# 8x8matrix_alt.net
KiCad netlist of a schematic drawn in EAGLE
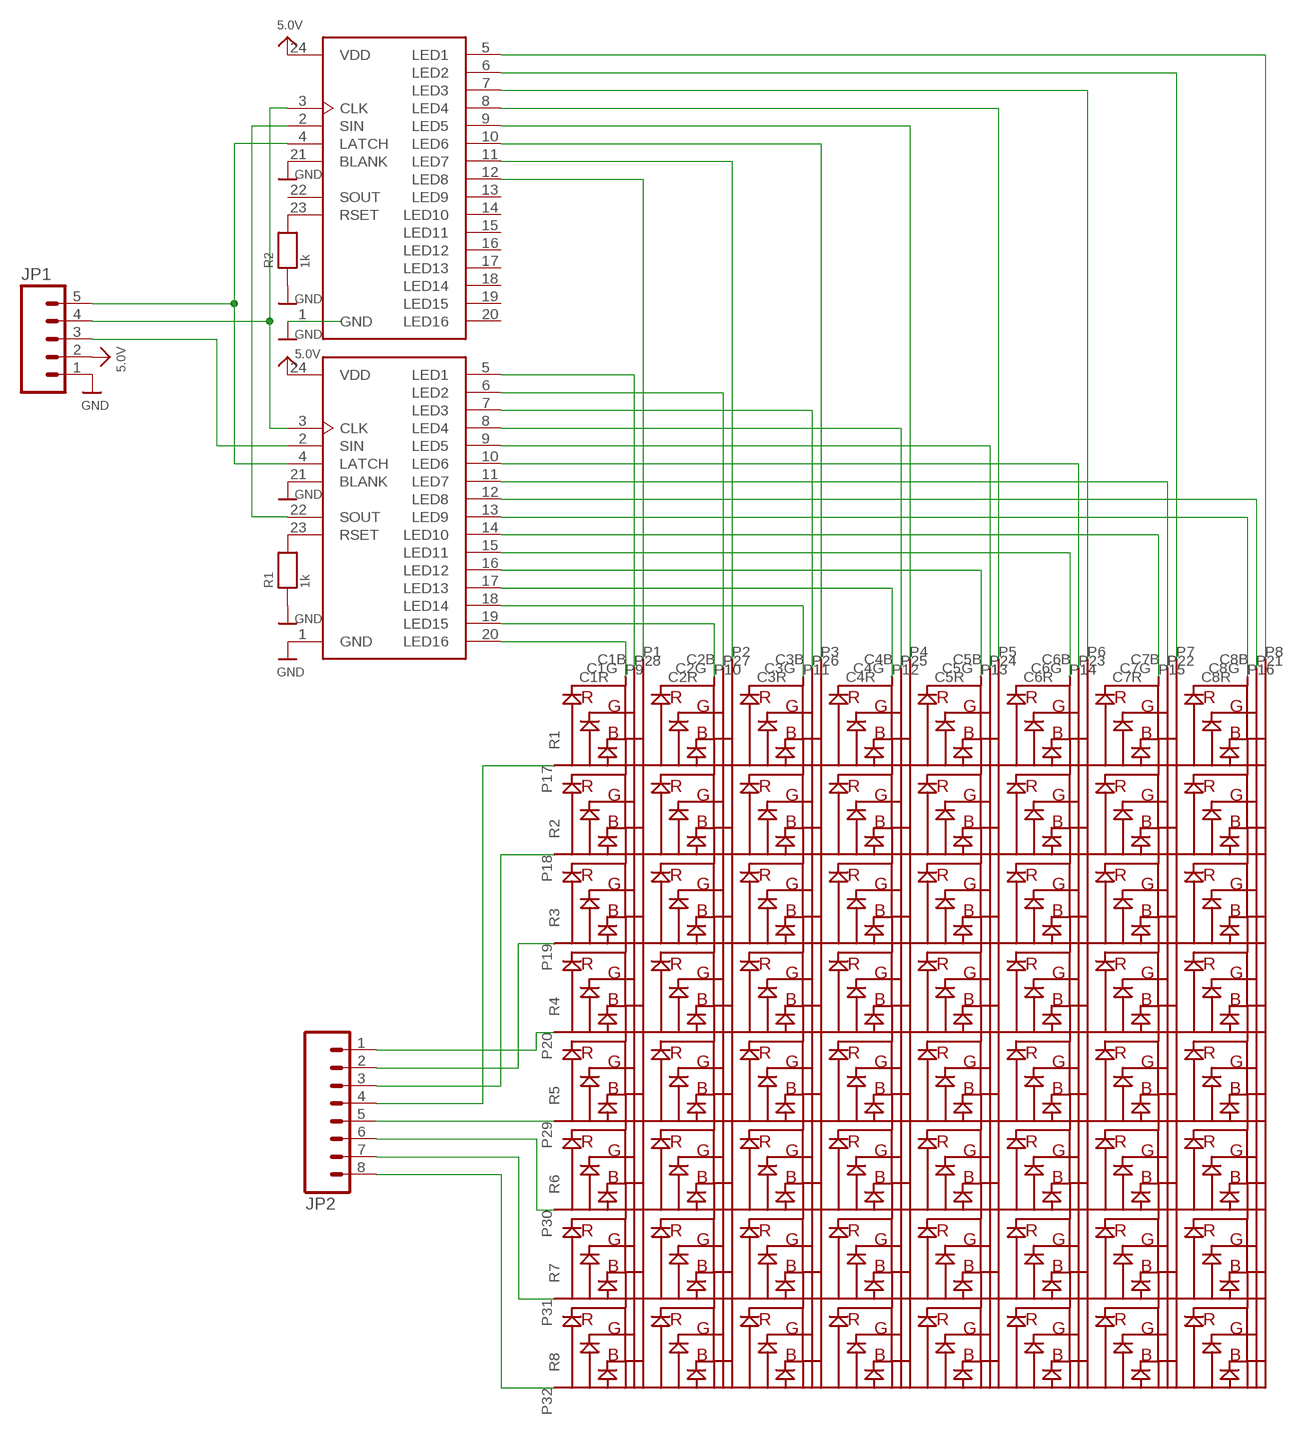
[diagram p0: schematic, sheet 1]

(export (version "E")
  (design (tool "Eeschema 10.0.6"))
  (components
    (comp (ref "JP1")
      (value "M05PTH")
      (footprint "eagle-import:1X05")
      (libsource (lib "eagle-import") (part "M05PTH"))
    )
    (comp (ref "JP2")
      (value "M081X08")
      (footprint "eagle-import:1X08")
      (libsource (lib "eagle-import") (part "M081X08"))
    )
    (comp (ref "R1")
      (value "1k")
      (footprint "eagle-import:0805_NOTHERMALS")
      (libsource (lib "eagle-import") (part "RESISTOR0805_NOTHERMALS"))
    )
    (comp (ref "R2")
      (value "1k")
      (footprint "eagle-import:0805_NOTHERMALS")
      (libsource (lib "eagle-import") (part "RESISTOR0805_NOTHERMALS"))
    )
    (comp (ref "U$1")
      (value "GTM2088ARGB")
      (footprint "eagle-import:8X8MATRIX")
      (libsource (lib "eagle-import") (part "GTM2088ARGB"))
    )
    (comp (ref "U$2")
      (value "CAT4016W")
      (footprint "eagle-import:TSSOP24")
      (libsource (lib "eagle-import") (part "CAT4016W"))
    )
    (comp (ref "U$3")
      (value "CAT4016W")
      (footprint "eagle-import:TSSOP24")
      (libsource (lib "eagle-import") (part "CAT4016W"))
    )
  )
  (nets
    (net (code "1") (name "5.0V") (class "Default")
      (node (ref "JP1") (pin "2") (pinfunction "2_2") (pintype "passive"))
      (node (ref "U$2") (pin "24") (pinfunction "VDD_24") (pintype "bidirectional"))
      (node (ref "U$3") (pin "24") (pinfunction "VDD_24") (pintype "bidirectional"))
    )
    (net (code "2") (name "GND") (class "Default")
      (node (ref "JP1") (pin "1") (pinfunction "1_1") (pintype "passive"))
      (node (ref "R1") (pin "1") (pinfunction "1_1") (pintype "passive"))
      (node (ref "R2") (pin "1") (pinfunction "1_1") (pintype "passive"))
      (node (ref "U$2") (pin "1") (pinfunction "GND_1") (pintype "bidirectional"))
      (node (ref "U$2") (pin "21") (pinfunction "BLANK_21") (pintype "bidirectional"))
      (node (ref "U$3") (pin "1") (pinfunction "GND_1") (pintype "bidirectional"))
      (node (ref "U$3") (pin "21") (pinfunction "BLANK_21") (pintype "bidirectional"))
    )
    (net (code "3") (name "Net-(U$1-C1B)") (class "Default")
      (node (ref "U$1") (pin "P1") (pinfunction "C1B_P1") (pintype "bidirectional"))
      (node (ref "U$2") (pin "12") (pinfunction "LED8_12") (pintype "bidirectional"))
    )
    (net (code "4") (name "Net-(U$1-C1G)") (class "Default")
      (node (ref "U$1") (pin "P28") (pinfunction "C1G_P28") (pintype "bidirectional"))
      (node (ref "U$3") (pin "5") (pinfunction "LED1_5") (pintype "bidirectional"))
    )
    (net (code "5") (name "Net-(U$1-C1R)") (class "Default")
      (node (ref "U$1") (pin "P9") (pinfunction "C1R_P9") (pintype "bidirectional"))
      (node (ref "U$3") (pin "20") (pinfunction "LED16_20") (pintype "bidirectional"))
    )
    (net (code "6") (name "Net-(U$1-C2B)") (class "Default")
      (node (ref "U$1") (pin "P2") (pinfunction "C2B_P2") (pintype "bidirectional"))
      (node (ref "U$2") (pin "11") (pinfunction "LED7_11") (pintype "bidirectional"))
    )
    (net (code "7") (name "Net-(U$1-C2G)") (class "Default")
      (node (ref "U$1") (pin "P27") (pinfunction "C2G_P27") (pintype "bidirectional"))
      (node (ref "U$3") (pin "6") (pinfunction "LED2_6") (pintype "bidirectional"))
    )
    (net (code "8") (name "Net-(U$1-C2R)") (class "Default")
      (node (ref "U$1") (pin "P10") (pinfunction "C2R_P10") (pintype "bidirectional"))
      (node (ref "U$3") (pin "19") (pinfunction "LED15_19") (pintype "bidirectional"))
    )
    (net (code "9") (name "Net-(U$1-C3B)") (class "Default")
      (node (ref "U$1") (pin "P3") (pinfunction "C3B_P3") (pintype "bidirectional"))
      (node (ref "U$2") (pin "10") (pinfunction "LED6_10") (pintype "bidirectional"))
    )
    (net (code "10") (name "Net-(U$1-C3G)") (class "Default")
      (node (ref "U$1") (pin "P26") (pinfunction "C3G_P26") (pintype "bidirectional"))
      (node (ref "U$3") (pin "7") (pinfunction "LED3_7") (pintype "bidirectional"))
    )
    (net (code "11") (name "Net-(U$1-C3R)") (class "Default")
      (node (ref "U$1") (pin "P11") (pinfunction "C3R_P11") (pintype "bidirectional"))
      (node (ref "U$3") (pin "18") (pinfunction "LED14_18") (pintype "bidirectional"))
    )
    (net (code "12") (name "Net-(U$1-C4B)") (class "Default")
      (node (ref "U$1") (pin "P4") (pinfunction "C4B_P4") (pintype "bidirectional"))
      (node (ref "U$2") (pin "9") (pinfunction "LED5_9") (pintype "bidirectional"))
    )
    (net (code "13") (name "Net-(U$1-C4G)") (class "Default")
      (node (ref "U$1") (pin "P25") (pinfunction "C4G_P25") (pintype "bidirectional"))
      (node (ref "U$3") (pin "8") (pinfunction "LED4_8") (pintype "bidirectional"))
    )
    (net (code "14") (name "Net-(U$1-C4R)") (class "Default")
      (node (ref "U$1") (pin "P12") (pinfunction "C4R_P12") (pintype "bidirectional"))
      (node (ref "U$3") (pin "17") (pinfunction "LED13_17") (pintype "bidirectional"))
    )
    (net (code "15") (name "Net-(U$1-C5B)") (class "Default")
      (node (ref "U$1") (pin "P5") (pinfunction "C5B_P5") (pintype "bidirectional"))
      (node (ref "U$2") (pin "8") (pinfunction "LED4_8") (pintype "bidirectional"))
    )
    (net (code "16") (name "Net-(U$1-C5G)") (class "Default")
      (node (ref "U$1") (pin "P24") (pinfunction "C5G_P24") (pintype "bidirectional"))
      (node (ref "U$3") (pin "9") (pinfunction "LED5_9") (pintype "bidirectional"))
    )
    (net (code "17") (name "Net-(U$1-C5R)") (class "Default")
      (node (ref "U$1") (pin "P13") (pinfunction "C5R_P13") (pintype "bidirectional"))
      (node (ref "U$3") (pin "16") (pinfunction "LED12_16") (pintype "bidirectional"))
    )
    (net (code "18") (name "Net-(U$1-C6B)") (class "Default")
      (node (ref "U$1") (pin "P6") (pinfunction "C6B_P6") (pintype "bidirectional"))
      (node (ref "U$2") (pin "7") (pinfunction "LED3_7") (pintype "bidirectional"))
    )
    (net (code "19") (name "Net-(U$1-C6G)") (class "Default")
      (node (ref "U$1") (pin "P23") (pinfunction "C6G_P23") (pintype "bidirectional"))
      (node (ref "U$3") (pin "10") (pinfunction "LED6_10") (pintype "bidirectional"))
    )
    (net (code "20") (name "Net-(U$1-C6R)") (class "Default")
      (node (ref "U$1") (pin "P14") (pinfunction "C6R_P14") (pintype "bidirectional"))
      (node (ref "U$3") (pin "15") (pinfunction "LED11_15") (pintype "bidirectional"))
    )
    (net (code "21") (name "Net-(U$1-C7B)") (class "Default")
      (node (ref "U$1") (pin "P7") (pinfunction "C7B_P7") (pintype "bidirectional"))
      (node (ref "U$2") (pin "6") (pinfunction "LED2_6") (pintype "bidirectional"))
    )
    (net (code "22") (name "Net-(U$1-C7G)") (class "Default")
      (node (ref "U$1") (pin "P22") (pinfunction "C7G_P22") (pintype "bidirectional"))
      (node (ref "U$3") (pin "11") (pinfunction "LED7_11") (pintype "bidirectional"))
    )
    (net (code "23") (name "Net-(U$1-C7R)") (class "Default")
      (node (ref "U$1") (pin "P15") (pinfunction "C7R_P15") (pintype "bidirectional"))
      (node (ref "U$3") (pin "14") (pinfunction "LED10_14") (pintype "bidirectional"))
    )
    (net (code "24") (name "Net-(U$1-C8B)") (class "Default")
      (node (ref "U$1") (pin "P8") (pinfunction "C8B_P8") (pintype "bidirectional"))
      (node (ref "U$2") (pin "5") (pinfunction "LED1_5") (pintype "bidirectional"))
    )
    (net (code "25") (name "Net-(U$1-C8G)") (class "Default")
      (node (ref "U$1") (pin "P21") (pinfunction "C8G_P21") (pintype "bidirectional"))
      (node (ref "U$3") (pin "12") (pinfunction "LED8_12") (pintype "bidirectional"))
    )
    (net (code "26") (name "Net-(U$1-C8R)") (class "Default")
      (node (ref "U$1") (pin "P16") (pinfunction "C8R_P16") (pintype "bidirectional"))
      (node (ref "U$3") (pin "13") (pinfunction "LED9_13") (pintype "bidirectional"))
    )
    (net (code "27") (name "Net-(U$1-R1)") (class "Default")
      (node (ref "JP2") (pin "4") (pinfunction "4_4") (pintype "passive"))
      (node (ref "U$1") (pin "P17") (pinfunction "R1_P17") (pintype "bidirectional"))
    )
    (net (code "28") (name "Net-(U$1-R2)") (class "Default")
      (node (ref "JP2") (pin "3") (pinfunction "3_3") (pintype "passive"))
      (node (ref "U$1") (pin "P18") (pinfunction "R2_P18") (pintype "bidirectional"))
    )
    (net (code "29") (name "Net-(U$1-R3)") (class "Default")
      (node (ref "JP2") (pin "2") (pinfunction "2_2") (pintype "passive"))
      (node (ref "U$1") (pin "P19") (pinfunction "R3_P19") (pintype "bidirectional"))
    )
    (net (code "30") (name "Net-(U$1-R4)") (class "Default")
      (node (ref "JP2") (pin "1") (pinfunction "1_1") (pintype "passive"))
      (node (ref "U$1") (pin "P20") (pinfunction "R4_P20") (pintype "bidirectional"))
    )
    (net (code "31") (name "Net-(U$1-R5)") (class "Default")
      (node (ref "JP2") (pin "5") (pinfunction "5_5") (pintype "passive"))
      (node (ref "U$1") (pin "P29") (pinfunction "R5_P29") (pintype "bidirectional"))
    )
    (net (code "32") (name "Net-(U$1-R6)") (class "Default")
      (node (ref "JP2") (pin "6") (pinfunction "6_6") (pintype "passive"))
      (node (ref "U$1") (pin "P30") (pinfunction "R6_P30") (pintype "bidirectional"))
    )
    (net (code "33") (name "Net-(U$1-R7)") (class "Default")
      (node (ref "JP2") (pin "7") (pinfunction "7_7") (pintype "passive"))
      (node (ref "U$1") (pin "P31") (pinfunction "R7_P31") (pintype "bidirectional"))
    )
    (net (code "34") (name "Net-(U$1-R8)") (class "Default")
      (node (ref "JP2") (pin "8") (pinfunction "8_8") (pintype "passive"))
      (node (ref "U$1") (pin "P32") (pinfunction "R8_P32") (pintype "bidirectional"))
    )
    (net (code "35") (name "Net-(U$2-CLK)") (class "Default")
      (node (ref "JP1") (pin "4") (pinfunction "4_4") (pintype "passive"))
      (node (ref "U$2") (pin "3") (pinfunction "CLK_3") (pintype "bidirectional"))
      (node (ref "U$3") (pin "3") (pinfunction "CLK_3") (pintype "bidirectional"))
    )
    (net (code "36") (name "Net-(U$2-LATCH)") (class "Default")
      (node (ref "JP1") (pin "5") (pinfunction "5_5") (pintype "passive"))
      (node (ref "U$2") (pin "4") (pinfunction "LATCH_4") (pintype "bidirectional"))
      (node (ref "U$3") (pin "4") (pinfunction "LATCH_4") (pintype "bidirectional"))
    )
    (net (code "37") (name "Net-(U$2-RSET)") (class "Default")
      (node (ref "R2") (pin "2") (pinfunction "2_2") (pintype "passive"))
      (node (ref "U$2") (pin "23") (pinfunction "RSET_23") (pintype "bidirectional"))
    )
    (net (code "38") (name "Net-(U$2-SIN)") (class "Default")
      (node (ref "U$2") (pin "2") (pinfunction "SIN_2") (pintype "bidirectional"))
      (node (ref "U$3") (pin "22") (pinfunction "SOUT_22") (pintype "bidirectional"))
    )
    (net (code "39") (name "Net-(U$3-RSET)") (class "Default")
      (node (ref "R1") (pin "2") (pinfunction "2_2") (pintype "passive"))
      (node (ref "U$3") (pin "23") (pinfunction "RSET_23") (pintype "bidirectional"))
    )
    (net (code "40") (name "Net-(U$3-SIN)") (class "Default")
      (node (ref "JP1") (pin "3") (pinfunction "3_3") (pintype "passive"))
      (node (ref "U$3") (pin "2") (pinfunction "SIN_2") (pintype "bidirectional"))
    )
    (net (code "41") (name "unconnected-(U$2-LED9-Pad13)") (class "Default")
      (node (ref "U$2") (pin "13") (pinfunction "LED9_13") (pintype "bidirectional"))
    )
    (net (code "42") (name "unconnected-(U$2-LED10-Pad14)") (class "Default")
      (node (ref "U$2") (pin "14") (pinfunction "LED10_14") (pintype "bidirectional"))
    )
    (net (code "43") (name "unconnected-(U$2-LED11-Pad15)") (class "Default")
      (node (ref "U$2") (pin "15") (pinfunction "LED11_15") (pintype "bidirectional"))
    )
    (net (code "44") (name "unconnected-(U$2-LED12-Pad16)") (class "Default")
      (node (ref "U$2") (pin "16") (pinfunction "LED12_16") (pintype "bidirectional"))
    )
    (net (code "45") (name "unconnected-(U$2-LED13-Pad17)") (class "Default")
      (node (ref "U$2") (pin "17") (pinfunction "LED13_17") (pintype "bidirectional"))
    )
    (net (code "46") (name "unconnected-(U$2-LED14-Pad18)") (class "Default")
      (node (ref "U$2") (pin "18") (pinfunction "LED14_18") (pintype "bidirectional"))
    )
    (net (code "47") (name "unconnected-(U$2-LED15-Pad19)") (class "Default")
      (node (ref "U$2") (pin "19") (pinfunction "LED15_19") (pintype "bidirectional"))
    )
    (net (code "48") (name "unconnected-(U$2-LED16-Pad20)") (class "Default")
      (node (ref "U$2") (pin "20") (pinfunction "LED16_20") (pintype "bidirectional"))
    )
    (net (code "49") (name "unconnected-(U$2-SOUT-Pad22)") (class "Default")
      (node (ref "U$2") (pin "22") (pinfunction "SOUT_22") (pintype "bidirectional"))
    )
  )
)
